# MainBorad.net
KiCad netlist of a schematic drawn in Altium Designer
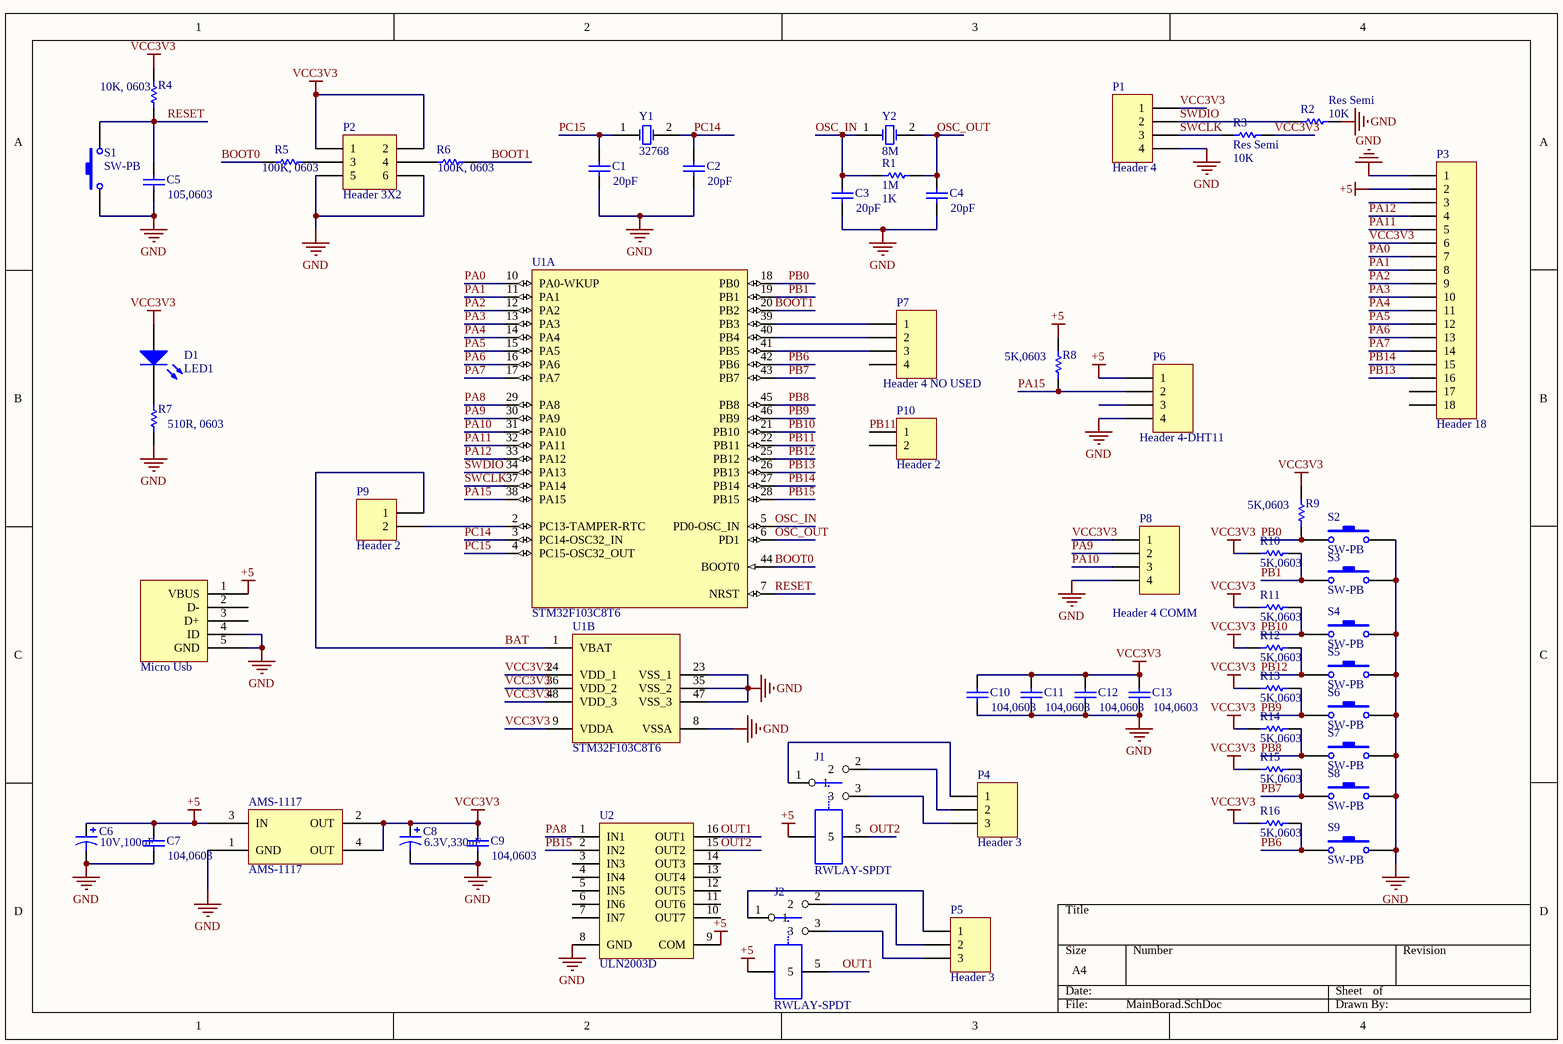
[diagram p0: MainBorad.SchDoc]

(export (version "E")
  (design (tool "Eeschema 10.0.6"))
  (components
    (comp (ref "AMS-1117")
      (value "AMS-1117")
      (footprint "SOT223")
      (libsource (lib "ams1117") (part "AMS-1117"))
    )
    (comp (ref "C1")
      (value "20pF")
      (footprint "0805C")
      (description "Capacitor (Semiconductor SIM Model)")
      (fields (field (name "Comment") "Cap Semi") (field (name "PUBLISHER") "Altium Limited"))
      (libsource (lib "Miscellaneous Devices") (part "Cap Semi"))
    )
    (comp (ref "C2")
      (value "20pF")
      (footprint "0805C")
      (description "Capacitor (Semiconductor SIM Model)")
      (fields (field (name "Comment") "Cap Semi") (field (name "PUBLISHER") "Altium Limited"))
      (libsource (lib "Miscellaneous Devices") (part "Cap Semi"))
    )
    (comp (ref "C3")
      (value "20pF")
      (footprint "0805C")
      (description "Capacitor (Semiconductor SIM Model)")
      (fields (field (name "Comment") "Cap Semi") (field (name "PUBLISHER") "Altium Limited"))
      (libsource (lib "Miscellaneous Devices") (part "Cap Semi"))
    )
    (comp (ref "C4")
      (value "20pF")
      (footprint "0805C")
      (description "Capacitor (Semiconductor SIM Model)")
      (fields (field (name "Comment") "Cap Semi") (field (name "PUBLISHER") "Altium Limited"))
      (libsource (lib "Miscellaneous Devices") (part "Cap Semi"))
    )
    (comp (ref "C5")
      (value "105,0603")
      (footprint "0805C")
      (description "Capacitor (Semiconductor SIM Model)")
      (fields (field (name "Comment") "Cap Semi") (field (name "PUBLISHER") "Altium Limited"))
      (libsource (lib "Miscellaneous Devices") (part "Cap Semi"))
    )
    (comp (ref "C6")
      (value "10V,100uF")
      (footprint "7343C")
      (description "Polarized Capacitor (Surface Mount)")
      (fields (field (name "Comment") "Cap Pol3") (field (name "PUBLISHER") "Altium Limited"))
      (libsource (lib "Miscellaneous Devices") (part "Cap Pol3"))
    )
    (comp (ref "C7")
      (value "104,0603")
      (footprint "0805C")
      (description "Capacitor (Semiconductor SIM Model)")
      (fields (field (name "Comment") "Cap Semi") (field (name "PUBLISHER") "Altium Limited"))
      (libsource (lib "Miscellaneous Devices") (part "Cap Semi"))
    )
    (comp (ref "C8")
      (value "6.3V,330uF")
      (footprint "7343C")
      (description "Polarized Capacitor (Surface Mount)")
      (fields (field (name "PUBLISHER") "Altium Limited"))
      (libsource (lib "Miscellaneous Devices") (part "Cap Pol3"))
    )
    (comp (ref "C9")
      (value "104,0603")
      (footprint "0805C")
      (description "Capacitor (Semiconductor SIM Model)")
      (fields (field (name "Comment") "Cap Semi") (field (name "PUBLISHER") "Altium Limited"))
      (libsource (lib "Miscellaneous Devices") (part "Cap Semi"))
    )
    (comp (ref "C10")
      (value "104,0603")
      (footprint "0805C")
      (description "Capacitor (Semiconductor SIM Model)")
      (fields (field (name "Comment") "Cap Semi") (field (name "PUBLISHER") "Altium Limited"))
      (libsource (lib "Miscellaneous Devices") (part "Cap Semi"))
    )
    (comp (ref "C11")
      (value "104,0603")
      (footprint "0805C")
      (description "Capacitor (Semiconductor SIM Model)")
      (fields (field (name "Comment") "Cap Semi") (field (name "PUBLISHER") "Altium Limited"))
      (libsource (lib "Miscellaneous Devices") (part "Cap Semi"))
    )
    (comp (ref "C12")
      (value "104,0603")
      (footprint "0805C")
      (description "Capacitor (Semiconductor SIM Model)")
      (fields (field (name "Comment") "Cap Semi") (field (name "PUBLISHER") "Altium Limited"))
      (libsource (lib "Miscellaneous Devices") (part "Cap Semi"))
    )
    (comp (ref "C13")
      (value "104,0603")
      (footprint "0805C")
      (description "Capacitor (Semiconductor SIM Model)")
      (fields (field (name "Comment") "Cap Semi") (field (name "PUBLISHER") "Altium Limited"))
      (libsource (lib "Miscellaneous Devices") (part "Cap Semi"))
    )
    (comp (ref "D1")
      (value "LED1")
      (footprint "0805")
      (description "Typical RED GaAs LED")
      (fields (field (name "PUBLISHER") "Altium Limited"))
      (libsource (lib "Miscellaneous Devices") (part "LED1"))
    )
    (comp (ref "J1") (value "RWLAY-SPDT") (footprint "relay") (libsource (lib "J继电器") (part "RWLAY-SPDT")))
    (comp (ref "J2") (value "RWLAY-SPDT") (footprint "relay") (libsource (lib "J继电器") (part "RWLAY-SPDT")))
    (comp (ref "Micro Usb")
      (value "Micro Usb")
      (footprint "Micro_USB")
      (libsource (lib "micro_usb") (part "Micro Usb"))
    )
    (comp (ref "P1")
      (value "Header 4")
      (footprint "HDR1X4")
      (description "Header, 4-Pin")
      (fields (field (name "PUBLISHER") "Altium Limited"))
      (libsource (lib "Miscellaneous Connectors") (part "Header 4"))
    )
    (comp (ref "P2")
      (value "Header 3X2")
      (footprint "HDR2X3")
      (description "Header, 3-Pin, Dual row")
      (fields (field (name "PUBLISHER") "Altium Limited"))
      (libsource (lib "Miscellaneous Connectors") (part "Header 3X2"))
    )
    (comp (ref "P3")
      (value "Header 18")
      (footprint "HDR1X18")
      (description "Header, 18-Pin")
      (fields (field (name "PUBLISHER") "Altium Limited"))
      (libsource (lib "Miscellaneous Connectors") (part "Header 18"))
    )
    (comp (ref "P4")
      (value "Header 3")
      (footprint "HDR1X3")
      (description "Header, 3-Pin")
      (fields (field (name "PUBLISHER") "Altium Limited"))
      (libsource (lib "Miscellaneous Connectors") (part "Header 3"))
    )
    (comp (ref "P5")
      (value "Header 3")
      (footprint "HDR1X3")
      (description "Header, 3-Pin")
      (fields (field (name "PUBLISHER") "Altium Limited"))
      (libsource (lib "Miscellaneous Connectors") (part "Header 3"))
    )
    (comp (ref "P6")
      (value "Header 4-DHT11")
      (footprint "HDR1X4")
      (description "Header, 4-Pin")
      (fields (field (name "PUBLISHER") "Altium Limited"))
      (libsource (lib "") (part "Header 4_1"))
    )
    (comp (ref "P7")
      (value "Header 4 NO USED")
      (footprint "HDR1X4")
      (description "Header, 4-Pin")
      (fields (field (name "PUBLISHER") "Altium Limited"))
      (libsource (lib "") (part "Header 4_1"))
    )
    (comp (ref "P8")
      (value "Header 4 COMM")
      (footprint "HDR1X4")
      (description "Header, 4-Pin")
      (fields (field (name "PUBLISHER") "Altium Limited"))
      (libsource (lib "") (part "Header 4_1"))
    )
    (comp (ref "P9")
      (value "Header 2")
      (footprint "HDR1X2")
      (description "Header, 2-Pin")
      (fields (field (name "PUBLISHER") "Altium Limited"))
      (libsource (lib "") (part "Header 2_1"))
    )
    (comp (ref "P10")
      (value "Header 2")
      (footprint "HDR1X2")
      (description "Header, 2-Pin")
      (fields (field (name "PUBLISHER") "Altium Limited"))
      (libsource (lib "Miscellaneous Connectors") (part "Header 2"))
    )
    (comp (ref "R1")
      (value "1M")
      (footprint "0805R")
      (description "Semiconductor Resistor")
      (fields (field (name "ALTIUM_VALUE") "1K") (field (name "PUBLISHER") "Altium Limited"))
      (libsource (lib "Miscellaneous Devices") (part "Res Semi"))
    )
    (comp (ref "R2")
      (value "Res Semi")
      (footprint "0805R")
      (description "Semiconductor Resistor")
      (fields (field (name "ALTIUM_VALUE") "10K") (field (name "PUBLISHER") "Altium Limited"))
      (libsource (lib "Miscellaneous Devices") (part "Res Semi"))
    )
    (comp (ref "R3")
      (value "Res Semi")
      (footprint "0805R")
      (description "Semiconductor Resistor")
      (fields (field (name "ALTIUM_VALUE") "10K") (field (name "PUBLISHER") "Altium Limited"))
      (libsource (lib "Miscellaneous Devices") (part "Res Semi"))
    )
    (comp (ref "R4")
      (value "10K, 0603")
      (footprint "0805R")
      (description "Semiconductor Resistor")
      (fields (field (name "Comment") "Res Semi") (field (name "PUBLISHER") "Altium Limited"))
      (libsource (lib "Miscellaneous Devices") (part "Res Semi"))
    )
    (comp (ref "R5")
      (value "100K, 0603")
      (footprint "0805R")
      (description "Semiconductor Resistor")
      (fields (field (name "Comment") "Res Semi") (field (name "PUBLISHER") "Altium Limited"))
      (libsource (lib "Miscellaneous Devices") (part "Res Semi"))
    )
    (comp (ref "R6")
      (value "100K, 0603")
      (footprint "0805R")
      (description "Semiconductor Resistor")
      (fields (field (name "Comment") "Res Semi") (field (name "PUBLISHER") "Altium Limited"))
      (libsource (lib "Miscellaneous Devices") (part "Res Semi"))
    )
    (comp (ref "R7")
      (value "510R, 0603")
      (footprint "0805R")
      (description "Semiconductor Resistor")
      (fields (field (name "Comment") "Res Semi") (field (name "PUBLISHER") "Altium Limited"))
      (libsource (lib "Miscellaneous Devices") (part "Res Semi"))
    )
    (comp (ref "R8")
      (value "5K,0603")
      (footprint "0805R")
      (description "Semiconductor Resistor")
      (fields (field (name "Comment") "Res Semi") (field (name "PUBLISHER") "Altium Limited"))
      (libsource (lib "Miscellaneous Devices") (part "Res Semi"))
    )
    (comp (ref "R9")
      (value "5K,0603")
      (footprint "0805R")
      (description "Semiconductor Resistor")
      (fields (field (name "Comment") "Res Semi") (field (name "PUBLISHER") "Altium Limited"))
      (libsource (lib "Miscellaneous Devices") (part "Res Semi"))
    )
    (comp (ref "R10")
      (value "5K,0603")
      (footprint "0805R")
      (description "Semiconductor Resistor")
      (fields (field (name "Comment") "Res Semi") (field (name "PUBLISHER") "Altium Limited"))
      (libsource (lib "Miscellaneous Devices") (part "Res Semi"))
    )
    (comp (ref "R11")
      (value "5K,0603")
      (footprint "0805R")
      (description "Semiconductor Resistor")
      (fields (field (name "Comment") "Res Semi") (field (name "PUBLISHER") "Altium Limited"))
      (libsource (lib "Miscellaneous Devices") (part "Res Semi"))
    )
    (comp (ref "R12")
      (value "5K,0603")
      (footprint "0805R")
      (description "Semiconductor Resistor")
      (fields (field (name "Comment") "Res Semi") (field (name "PUBLISHER") "Altium Limited"))
      (libsource (lib "Miscellaneous Devices") (part "Res Semi"))
    )
    (comp (ref "R13")
      (value "5K,0603")
      (footprint "0805R")
      (description "Semiconductor Resistor")
      (fields (field (name "Comment") "Res Semi") (field (name "PUBLISHER") "Altium Limited"))
      (libsource (lib "Miscellaneous Devices") (part "Res Semi"))
    )
    (comp (ref "R14")
      (value "5K,0603")
      (footprint "0805R")
      (description "Semiconductor Resistor")
      (fields (field (name "Comment") "Res Semi") (field (name "PUBLISHER") "Altium Limited"))
      (libsource (lib "Miscellaneous Devices") (part "Res Semi"))
    )
    (comp (ref "R15")
      (value "5K,0603")
      (footprint "0805R")
      (description "Semiconductor Resistor")
      (fields (field (name "Comment") "Res Semi") (field (name "PUBLISHER") "Altium Limited"))
      (libsource (lib "Miscellaneous Devices") (part "Res Semi"))
    )
    (comp (ref "R16")
      (value "5K,0603")
      (footprint "0805R")
      (description "Semiconductor Resistor")
      (fields (field (name "Comment") "Res Semi") (field (name "PUBLISHER") "Altium Limited"))
      (libsource (lib "Miscellaneous Devices") (part "Res Semi"))
    )
    (comp (ref "S1")
      (value "SW-PB")
      (footprint "SPST-2")
      (description "Switch")
      (fields (field (name "PUBLISHER") "Altium Limited"))
      (libsource (lib "Miscellaneous Devices") (part "SW-PB"))
    )
    (comp (ref "S2")
      (value "SW-PB")
      (footprint "SPST-2")
      (description "Switch")
      (fields (field (name "PUBLISHER") "Altium Limited"))
      (libsource (lib "Miscellaneous Devices") (part "SW-PB"))
    )
    (comp (ref "S3")
      (value "SW-PB")
      (footprint "SPST-2")
      (description "Switch")
      (fields (field (name "PUBLISHER") "Altium Limited"))
      (libsource (lib "Miscellaneous Devices") (part "SW-PB"))
    )
    (comp (ref "S4")
      (value "SW-PB")
      (footprint "SPST-2")
      (description "Switch")
      (fields (field (name "PUBLISHER") "Altium Limited"))
      (libsource (lib "Miscellaneous Devices") (part "SW-PB"))
    )
    (comp (ref "S5")
      (value "SW-PB")
      (footprint "SPST-2")
      (description "Switch")
      (fields (field (name "PUBLISHER") "Altium Limited"))
      (libsource (lib "Miscellaneous Devices") (part "SW-PB"))
    )
    (comp (ref "S6")
      (value "SW-PB")
      (footprint "SPST-2")
      (description "Switch")
      (fields (field (name "PUBLISHER") "Altium Limited"))
      (libsource (lib "Miscellaneous Devices") (part "SW-PB"))
    )
    (comp (ref "S7")
      (value "SW-PB")
      (footprint "SPST-2")
      (description "Switch")
      (fields (field (name "PUBLISHER") "Altium Limited"))
      (libsource (lib "Miscellaneous Devices") (part "SW-PB"))
    )
    (comp (ref "S8")
      (value "SW-PB")
      (footprint "SPST-2")
      (description "Switch")
      (fields (field (name "PUBLISHER") "Altium Limited"))
      (libsource (lib "Miscellaneous Devices") (part "SW-PB"))
    )
    (comp (ref "S9")
      (value "SW-PB")
      (footprint "SPST-2")
      (description "Switch")
      (fields (field (name "PUBLISHER") "Altium Limited"))
      (libsource (lib "Miscellaneous Devices") (part "SW-PB"))
    )
    (comp (ref "U1")
      (value "STM32F103C8T6")
      (footprint "LQFP48_N")
      (libsource (lib "STMicroelectronics STM32 F1") (part "STM32F103C8T6"))
    )
    (comp (ref "U2")
      (value "ULN2003D")
      (footprint "SO16_N")
      (description "Seven Darlington Array")
      (fields (field (name "PUBLISHER") "Altium Limited"))
      (libsource (lib "ST Interface Darlington Driver") (part "ULN2003D"))
    )
    (comp (ref "Y1")
      (value "32768")
      (footprint "R38")
      (description "Crystal Oscillator")
      (fields (field (name "PUBLISHER") "Altium Limited"))
      (libsource (lib "Miscellaneous Devices") (part "XTAL"))
    )
    (comp (ref "Y2")
      (value "8M")
      (footprint "XTAL1")
      (description "Crystal Oscillator")
      (fields (field (name "PUBLISHER") "Altium Limited"))
      (libsource (lib "Miscellaneous Devices") (part "XTAL"))
    )
  )
  (nets
    (net (code "1") (name "+5") (class "Default")
      (node (ref "AMS-1117") (pin "3") (pinfunction "IN_3") (pintype "passive"))
      (node (ref "C6") (pin "1") (pinfunction "1_1") (pintype "passive"))
      (node (ref "C7") (pin "2") (pinfunction "2_2") (pintype "passive"))
      (node (ref "J1") (pin "4") (pinfunction "4_4") (pintype "passive"))
      (node (ref "J2") (pin "4") (pinfunction "4_4") (pintype "passive"))
      (node (ref "Micro Usb") (pin "1") (pinfunction "VBUS_1") (pintype "passive"))
      (node (ref "P3") (pin "2") (pinfunction "2_2") (pintype "passive"))
      (node (ref "P6") (pin "1") (pinfunction "1_1") (pintype "passive"))
      (node (ref "R8") (pin "2") (pinfunction "2_2") (pintype "passive"))
      (node (ref "U2") (pin "9") (pinfunction "COM_9") (pintype "passive"))
    )
    (net (code "2") (name "/BAT") (class "Default")
      (node (ref "P9") (pin "1") (pinfunction "1_1") (pintype "passive"))
      (node (ref "U1") (pin "1") (pinfunction "VBAT_1") (pintype "power_in"))
    )
    (net (code "3") (name "/BOOT0") (class "Default")
      (node (ref "R5") (pin "2") (pinfunction "2_2") (pintype "passive"))
      (node (ref "U1") (pin "44") (pinfunction "BOOT0_44") (pintype "input"))
    )
    (net (code "4") (name "/BOOT1") (class "Default")
      (node (ref "R6") (pin "1") (pinfunction "1_1") (pintype "passive"))
      (node (ref "U1") (pin "20") (pinfunction "PB2_20") (pintype "bidirectional"))
    )
    (net (code "5") (name "/OSC_IN") (class "Default")
      (node (ref "C3") (pin "2") (pinfunction "2_2") (pintype "passive"))
      (node (ref "R1") (pin "1") (pinfunction "1_1") (pintype "passive"))
      (node (ref "U1") (pin "5") (pinfunction "PD0-OSC_IN_5") (pintype "bidirectional"))
      (node (ref "Y2") (pin "1") (pinfunction "OSC1_1") (pintype "passive"))
    )
    (net (code "6") (name "/OSC_OUT") (class "Default")
      (node (ref "C4") (pin "2") (pinfunction "2_2") (pintype "passive"))
      (node (ref "R1") (pin "2") (pinfunction "2_2") (pintype "passive"))
      (node (ref "U1") (pin "6") (pinfunction "PD1_6") (pintype "bidirectional"))
      (node (ref "Y2") (pin "2") (pinfunction "OSC2_2") (pintype "passive"))
    )
    (net (code "7") (name "/OUT1") (class "Default")
      (node (ref "J2") (pin "5") (pinfunction "5_5") (pintype "passive"))
      (node (ref "U2") (pin "16") (pinfunction "OUT1_16") (pintype "open_collector"))
    )
    (net (code "8") (name "/OUT2") (class "Default")
      (node (ref "J1") (pin "5") (pinfunction "5_5") (pintype "passive"))
      (node (ref "U2") (pin "15") (pinfunction "OUT2_15") (pintype "open_collector"))
    )
    (net (code "9") (name "/PA0") (class "Default")
      (node (ref "P3") (pin "7") (pinfunction "7_7") (pintype "passive"))
      (node (ref "U1") (pin "10") (pinfunction "PA0-WKUP_10") (pintype "bidirectional"))
    )
    (net (code "10") (name "/PA1") (class "Default")
      (node (ref "P3") (pin "8") (pinfunction "8_8") (pintype "passive"))
      (node (ref "U1") (pin "11") (pinfunction "PA1_11") (pintype "bidirectional"))
    )
    (net (code "11") (name "/PA2") (class "Default")
      (node (ref "P3") (pin "9") (pinfunction "9_9") (pintype "passive"))
      (node (ref "U1") (pin "12") (pinfunction "PA2_12") (pintype "bidirectional"))
    )
    (net (code "12") (name "/PA3") (class "Default")
      (node (ref "P3") (pin "10") (pinfunction "10_10") (pintype "passive"))
      (node (ref "U1") (pin "13") (pinfunction "PA3_13") (pintype "bidirectional"))
    )
    (net (code "13") (name "/PA4") (class "Default")
      (node (ref "P3") (pin "11") (pinfunction "11_11") (pintype "passive"))
      (node (ref "U1") (pin "14") (pinfunction "PA4_14") (pintype "bidirectional"))
    )
    (net (code "14") (name "/PA5") (class "Default")
      (node (ref "P3") (pin "12") (pinfunction "12_12") (pintype "passive"))
      (node (ref "U1") (pin "15") (pinfunction "PA5_15") (pintype "bidirectional"))
    )
    (net (code "15") (name "/PA6") (class "Default")
      (node (ref "P3") (pin "13") (pinfunction "13_13") (pintype "passive"))
      (node (ref "U1") (pin "16") (pinfunction "PA6_16") (pintype "bidirectional"))
    )
    (net (code "16") (name "/PA7") (class "Default")
      (node (ref "P3") (pin "14") (pinfunction "14_14") (pintype "passive"))
      (node (ref "U1") (pin "17") (pinfunction "PA7_17") (pintype "bidirectional"))
    )
    (net (code "17") (name "/PA8") (class "Default")
      (node (ref "U1") (pin "29") (pinfunction "PA8_29") (pintype "bidirectional"))
      (node (ref "U2") (pin "1") (pinfunction "IN1_1") (pintype "passive"))
    )
    (net (code "18") (name "/PA9") (class "Default")
      (node (ref "P8") (pin "2") (pinfunction "2_2") (pintype "passive"))
      (node (ref "U1") (pin "30") (pinfunction "PA9_30") (pintype "bidirectional"))
    )
    (net (code "19") (name "/PA10") (class "Default")
      (node (ref "P8") (pin "3") (pinfunction "3_3") (pintype "passive"))
      (node (ref "U1") (pin "31") (pinfunction "PA10_31") (pintype "bidirectional"))
    )
    (net (code "20") (name "/PA11") (class "Default")
      (node (ref "P3") (pin "5") (pinfunction "5_5") (pintype "passive"))
      (node (ref "U1") (pin "32") (pinfunction "PA11_32") (pintype "bidirectional"))
    )
    (net (code "21") (name "/PA12") (class "Default")
      (node (ref "P3") (pin "4") (pinfunction "4_4") (pintype "passive"))
      (node (ref "U1") (pin "33") (pinfunction "PA12_33") (pintype "bidirectional"))
    )
    (net (code "22") (name "/PA15") (class "Default")
      (node (ref "P6") (pin "2") (pinfunction "2_2") (pintype "passive"))
      (node (ref "R8") (pin "1") (pinfunction "1_1") (pintype "passive"))
      (node (ref "U1") (pin "38") (pinfunction "PA15_38") (pintype "bidirectional"))
    )
    (net (code "23") (name "/PB0") (class "Default")
      (node (ref "R9") (pin "1") (pinfunction "1_1") (pintype "passive"))
      (node (ref "S2") (pin "1") (pinfunction "1_1") (pintype "passive"))
      (node (ref "U1") (pin "18") (pinfunction "PB0_18") (pintype "bidirectional"))
    )
    (net (code "24") (name "/PB1") (class "Default")
      (node (ref "R10") (pin "1") (pinfunction "1_1") (pintype "passive"))
      (node (ref "S3") (pin "1") (pinfunction "1_1") (pintype "passive"))
      (node (ref "U1") (pin "19") (pinfunction "PB1_19") (pintype "bidirectional"))
    )
    (net (code "25") (name "/PB6") (class "Default")
      (node (ref "R16") (pin "1") (pinfunction "1_1") (pintype "passive"))
      (node (ref "S9") (pin "1") (pinfunction "1_1") (pintype "passive"))
      (node (ref "U1") (pin "42") (pinfunction "PB6_42") (pintype "bidirectional"))
    )
    (net (code "26") (name "/PB7") (class "Default")
      (node (ref "R15") (pin "1") (pinfunction "1_1") (pintype "passive"))
      (node (ref "S8") (pin "1") (pinfunction "1_1") (pintype "passive"))
      (node (ref "U1") (pin "43") (pinfunction "PB7_43") (pintype "bidirectional"))
    )
    (net (code "27") (name "/PB8") (class "Default")
      (node (ref "R14") (pin "1") (pinfunction "1_1") (pintype "passive"))
      (node (ref "S7") (pin "1") (pinfunction "1_1") (pintype "passive"))
      (node (ref "U1") (pin "45") (pinfunction "PB8_45") (pintype "bidirectional"))
    )
    (net (code "28") (name "/PB9") (class "Default")
      (node (ref "R13") (pin "1") (pinfunction "1_1") (pintype "passive"))
      (node (ref "S6") (pin "1") (pinfunction "1_1") (pintype "passive"))
      (node (ref "U1") (pin "46") (pinfunction "PB9_46") (pintype "bidirectional"))
    )
    (net (code "29") (name "/PB10") (class "Default")
      (node (ref "R11") (pin "1") (pinfunction "1_1") (pintype "passive"))
      (node (ref "S4") (pin "1") (pinfunction "1_1") (pintype "passive"))
      (node (ref "U1") (pin "21") (pinfunction "PB10_21") (pintype "bidirectional"))
    )
    (net (code "30") (name "/PB11") (class "Default")
      (node (ref "P10") (pin "1") (pinfunction "1_1") (pintype "passive"))
      (node (ref "U1") (pin "22") (pinfunction "PB11_22") (pintype "bidirectional"))
    )
    (net (code "31") (name "/PB12") (class "Default")
      (node (ref "R12") (pin "1") (pinfunction "1_1") (pintype "passive"))
      (node (ref "S5") (pin "1") (pinfunction "1_1") (pintype "passive"))
      (node (ref "U1") (pin "25") (pinfunction "PB12_25") (pintype "bidirectional"))
    )
    (net (code "32") (name "/PB13") (class "Default")
      (node (ref "P3") (pin "16") (pinfunction "16_16") (pintype "passive"))
      (node (ref "U1") (pin "26") (pinfunction "PB13_26") (pintype "bidirectional"))
    )
    (net (code "33") (name "/PB14") (class "Default")
      (node (ref "P3") (pin "15") (pinfunction "15_15") (pintype "passive"))
      (node (ref "U1") (pin "27") (pinfunction "PB14_27") (pintype "bidirectional"))
    )
    (net (code "34") (name "/PB15") (class "Default")
      (node (ref "U1") (pin "28") (pinfunction "PB15_28") (pintype "bidirectional"))
      (node (ref "U2") (pin "2") (pinfunction "IN2_2") (pintype "passive"))
    )
    (net (code "35") (name "/PC14") (class "Default")
      (node (ref "C2") (pin "2") (pinfunction "2_2") (pintype "passive"))
      (node (ref "U1") (pin "3") (pinfunction "PC14-OSC32_IN_3") (pintype "bidirectional"))
      (node (ref "Y1") (pin "2") (pinfunction "OSC2_2") (pintype "passive"))
    )
    (net (code "36") (name "/PC15") (class "Default")
      (node (ref "C1") (pin "2") (pinfunction "2_2") (pintype "passive"))
      (node (ref "U1") (pin "4") (pinfunction "PC15-OSC32_OUT_4") (pintype "bidirectional"))
      (node (ref "Y1") (pin "1") (pinfunction "OSC1_1") (pintype "passive"))
    )
    (net (code "37") (name "/RESET") (class "Default")
      (node (ref "C5") (pin "2") (pinfunction "2_2") (pintype "passive"))
      (node (ref "R4") (pin "1") (pinfunction "1_1") (pintype "passive"))
      (node (ref "S1") (pin "2") (pinfunction "2_2") (pintype "passive"))
      (node (ref "U1") (pin "7") (pinfunction "NRST_7") (pintype "bidirectional"))
    )
    (net (code "38") (name "/SWCLK") (class "Default")
      (node (ref "P1") (pin "3") (pinfunction "3_3") (pintype "passive"))
      (node (ref "R3") (pin "2") (pinfunction "2_2") (pintype "passive"))
      (node (ref "U1") (pin "37") (pinfunction "PA14_37") (pintype "bidirectional"))
    )
    (net (code "39") (name "/SWDIO") (class "Default")
      (node (ref "P1") (pin "2") (pinfunction "2_2") (pintype "passive"))
      (node (ref "R2") (pin "2") (pinfunction "2_2") (pintype "passive"))
      (node (ref "U1") (pin "34") (pinfunction "PA13_34") (pintype "bidirectional"))
    )
    (net (code "40") (name "GND") (class "Default")
      (node (ref "AMS-1117") (pin "1") (pinfunction "GND_1") (pintype "power_in"))
      (node (ref "C1") (pin "1") (pinfunction "1_1") (pintype "passive"))
      (node (ref "C10") (pin "1") (pinfunction "1_1") (pintype "passive"))
      (node (ref "C11") (pin "1") (pinfunction "1_1") (pintype "passive"))
      (node (ref "C12") (pin "1") (pinfunction "1_1") (pintype "passive"))
      (node (ref "C13") (pin "1") (pinfunction "1_1") (pintype "passive"))
      (node (ref "C2") (pin "1") (pinfunction "1_1") (pintype "passive"))
      (node (ref "C3") (pin "1") (pinfunction "1_1") (pintype "passive"))
      (node (ref "C4") (pin "1") (pinfunction "1_1") (pintype "passive"))
      (node (ref "C5") (pin "1") (pinfunction "1_1") (pintype "passive"))
      (node (ref "C6") (pin "2") (pinfunction "2_2") (pintype "passive"))
      (node (ref "C7") (pin "1") (pinfunction "1_1") (pintype "passive"))
      (node (ref "C8") (pin "2") (pinfunction "2_2") (pintype "passive"))
      (node (ref "C9") (pin "1") (pinfunction "1_1") (pintype "passive"))
      (node (ref "Micro Usb") (pin "4") (pinfunction "ID_4") (pintype "passive"))
      (node (ref "Micro Usb") (pin "5") (pinfunction "GND_5") (pintype "passive"))
      (node (ref "P1") (pin "4") (pinfunction "4_4") (pintype "passive"))
      (node (ref "P2") (pin "5") (pinfunction "5_5") (pintype "passive"))
      (node (ref "P2") (pin "6") (pinfunction "6_6") (pintype "passive"))
      (node (ref "P3") (pin "1") (pinfunction "1_1") (pintype "passive"))
      (node (ref "P6") (pin "4") (pinfunction "4_4") (pintype "passive"))
      (node (ref "P8") (pin "4") (pinfunction "4_4") (pintype "passive"))
      (node (ref "R2") (pin "1") (pinfunction "1_1") (pintype "passive"))
      (node (ref "R7") (pin "1") (pinfunction "1_1") (pintype "passive"))
      (node (ref "S1") (pin "1") (pinfunction "1_1") (pintype "passive"))
      (node (ref "S2") (pin "2") (pinfunction "2_2") (pintype "passive"))
      (node (ref "S3") (pin "2") (pinfunction "2_2") (pintype "passive"))
      (node (ref "S4") (pin "2") (pinfunction "2_2") (pintype "passive"))
      (node (ref "S5") (pin "2") (pinfunction "2_2") (pintype "passive"))
      (node (ref "S6") (pin "2") (pinfunction "2_2") (pintype "passive"))
      (node (ref "S7") (pin "2") (pinfunction "2_2") (pintype "passive"))
      (node (ref "S8") (pin "2") (pinfunction "2_2") (pintype "passive"))
      (node (ref "S9") (pin "2") (pinfunction "2_2") (pintype "passive"))
      (node (ref "U1") (pin "23") (pinfunction "VSS_1_23") (pintype "power_in"))
      (node (ref "U1") (pin "35") (pinfunction "VSS_2_35") (pintype "power_in"))
      (node (ref "U1") (pin "47") (pinfunction "VSS_3_47") (pintype "power_in"))
      (node (ref "U1") (pin "8") (pinfunction "VSSA_8") (pintype "power_in"))
      (node (ref "U2") (pin "8") (pinfunction "GND_8") (pintype "power_in"))
    )
    (net (code "41") (name "Net-(D1-K)") (class "Default")
      (node (ref "D1") (pin "2") (pinfunction "K_2") (pintype "passive"))
      (node (ref "R7") (pin "2") (pinfunction "2_2") (pintype "passive"))
    )
    (net (code "42") (name "Net-(J1-Pad1)") (class "Default")
      (node (ref "J1") (pin "1") (pinfunction "1_1") (pintype "passive"))
      (node (ref "P4") (pin "1") (pinfunction "1_1") (pintype "passive"))
    )
    (net (code "43") (name "Net-(J1-Pad2)") (class "Default")
      (node (ref "J1") (pin "2") (pinfunction "2_2") (pintype "passive"))
      (node (ref "P4") (pin "2") (pinfunction "2_2") (pintype "passive"))
    )
    (net (code "44") (name "Net-(J1-Pad3)") (class "Default")
      (node (ref "J1") (pin "3") (pinfunction "3_3") (pintype "passive"))
      (node (ref "P4") (pin "3") (pinfunction "3_3") (pintype "passive"))
    )
    (net (code "45") (name "Net-(J2-Pad1)") (class "Default")
      (node (ref "J2") (pin "1") (pinfunction "1_1") (pintype "passive"))
      (node (ref "P5") (pin "1") (pinfunction "1_1") (pintype "passive"))
    )
    (net (code "46") (name "Net-(J2-Pad2)") (class "Default")
      (node (ref "J2") (pin "2") (pinfunction "2_2") (pintype "passive"))
      (node (ref "P5") (pin "2") (pinfunction "2_2") (pintype "passive"))
    )
    (net (code "47") (name "Net-(J2-Pad3)") (class "Default")
      (node (ref "J2") (pin "3") (pinfunction "3_3") (pintype "passive"))
      (node (ref "P5") (pin "3") (pinfunction "3_3") (pintype "passive"))
    )
    (net (code "48") (name "Net-(P2-Pad3)") (class "Default")
      (node (ref "P2") (pin "3") (pinfunction "3_3") (pintype "passive"))
      (node (ref "R5") (pin "1") (pinfunction "1_1") (pintype "passive"))
    )
    (net (code "49") (name "Net-(P2-Pad4)") (class "Default")
      (node (ref "P2") (pin "4") (pinfunction "4_4") (pintype "passive"))
      (node (ref "R6") (pin "2") (pinfunction "2_2") (pintype "passive"))
    )
    (net (code "50") (name "Net-(U1A-PB3)") (class "Default")
      (node (ref "P7") (pin "1") (pinfunction "1_1") (pintype "passive"))
      (node (ref "U1") (pin "39") (pinfunction "PB3_39") (pintype "bidirectional"))
    )
    (net (code "51") (name "Net-(U1A-PB4)") (class "Default")
      (node (ref "P7") (pin "2") (pinfunction "2_2") (pintype "passive"))
      (node (ref "U1") (pin "40") (pinfunction "PB4_40") (pintype "bidirectional"))
    )
    (net (code "52") (name "Net-(U1A-PB5)") (class "Default")
      (node (ref "P7") (pin "3") (pinfunction "3_3") (pintype "passive"))
      (node (ref "U1") (pin "41") (pinfunction "PB5_41") (pintype "bidirectional"))
    )
    (net (code "53") (name "Net-(U1A-PC13-TAMPER-RTC)") (class "Default")
      (node (ref "P9") (pin "2") (pinfunction "2_2") (pintype "passive"))
      (node (ref "U1") (pin "2") (pinfunction "PC13-TAMPER-RTC_2") (pintype "bidirectional"))
    )
    (net (code "54") (name "VCC3V3") (class "Default")
      (node (ref "AMS-1117") (pin "2") (pinfunction "OUT_2") (pintype "passive"))
      (node (ref "AMS-1117") (pin "4") (pinfunction "OUT_4") (pintype "passive"))
      (node (ref "C10") (pin "2") (pinfunction "2_2") (pintype "passive"))
      (node (ref "C11") (pin "2") (pinfunction "2_2") (pintype "passive"))
      (node (ref "C12") (pin "2") (pinfunction "2_2") (pintype "passive"))
      (node (ref "C13") (pin "2") (pinfunction "2_2") (pintype "passive"))
      (node (ref "C8") (pin "1") (pinfunction "1_1") (pintype "passive"))
      (node (ref "C9") (pin "2") (pinfunction "2_2") (pintype "passive"))
      (node (ref "D1") (pin "1") (pinfunction "A_1") (pintype "passive"))
      (node (ref "P1") (pin "1") (pinfunction "1_1") (pintype "passive"))
      (node (ref "P2") (pin "1") (pinfunction "1_1") (pintype "passive"))
      (node (ref "P2") (pin "2") (pinfunction "2_2") (pintype "passive"))
      (node (ref "P3") (pin "6") (pinfunction "6_6") (pintype "passive"))
      (node (ref "P8") (pin "1") (pinfunction "1_1") (pintype "passive"))
      (node (ref "R10") (pin "2") (pinfunction "2_2") (pintype "passive"))
      (node (ref "R11") (pin "2") (pinfunction "2_2") (pintype "passive"))
      (node (ref "R12") (pin "2") (pinfunction "2_2") (pintype "passive"))
      (node (ref "R13") (pin "2") (pinfunction "2_2") (pintype "passive"))
      (node (ref "R14") (pin "2") (pinfunction "2_2") (pintype "passive"))
      (node (ref "R15") (pin "2") (pinfunction "2_2") (pintype "passive"))
      (node (ref "R16") (pin "2") (pinfunction "2_2") (pintype "passive"))
      (node (ref "R3") (pin "1") (pinfunction "1_1") (pintype "passive"))
      (node (ref "R4") (pin "2") (pinfunction "2_2") (pintype "passive"))
      (node (ref "R9") (pin "2") (pinfunction "2_2") (pintype "passive"))
      (node (ref "U1") (pin "24") (pinfunction "VDD_1_24") (pintype "power_in"))
      (node (ref "U1") (pin "36") (pinfunction "VDD_2_36") (pintype "power_in"))
      (node (ref "U1") (pin "48") (pinfunction "VDD_3_48") (pintype "power_in"))
      (node (ref "U1") (pin "9") (pinfunction "VDDA_9") (pintype "power_in"))
    )
    (net (code "55") (name "unconnected-(Micro Usb-D+-Pad3)") (class "Default")
      (node (ref "Micro Usb") (pin "3") (pinfunction "D+_3") (pintype "passive"))
    )
    (net (code "56") (name "unconnected-(Micro Usb-D--Pad2)") (class "Default")
      (node (ref "Micro Usb") (pin "2") (pinfunction "D-_2") (pintype "passive"))
    )
    (net (code "57") (name "unconnected-(P3-Pad3)") (class "Default")
      (node (ref "P3") (pin "3") (pinfunction "3_3") (pintype "passive"))
    )
    (net (code "58") (name "unconnected-(P3-Pad17)") (class "Default")
      (node (ref "P3") (pin "17") (pinfunction "17_17") (pintype "passive"))
    )
    (net (code "59") (name "unconnected-(P3-Pad18)") (class "Default")
      (node (ref "P3") (pin "18") (pinfunction "18_18") (pintype "passive"))
    )
    (net (code "60") (name "unconnected-(P6-Pad3)") (class "Default")
      (node (ref "P6") (pin "3") (pinfunction "3_3") (pintype "passive"))
    )
    (net (code "61") (name "unconnected-(P7-Pad4)") (class "Default")
      (node (ref "P7") (pin "4") (pinfunction "4_4") (pintype "passive"))
    )
    (net (code "62") (name "unconnected-(P10-Pad2)") (class "Default")
      (node (ref "P10") (pin "2") (pinfunction "2_2") (pintype "passive"))
    )
    (net (code "63") (name "unconnected-(U2-IN3-Pad3)") (class "Default")
      (node (ref "U2") (pin "3") (pinfunction "IN3_3") (pintype "passive"))
    )
    (net (code "64") (name "unconnected-(U2-IN4-Pad4)") (class "Default")
      (node (ref "U2") (pin "4") (pinfunction "IN4_4") (pintype "passive"))
    )
    (net (code "65") (name "unconnected-(U2-IN5-Pad5)") (class "Default")
      (node (ref "U2") (pin "5") (pinfunction "IN5_5") (pintype "passive"))
    )
    (net (code "66") (name "unconnected-(U2-IN6-Pad6)") (class "Default")
      (node (ref "U2") (pin "6") (pinfunction "IN6_6") (pintype "passive"))
    )
    (net (code "67") (name "unconnected-(U2-IN7-Pad7)") (class "Default")
      (node (ref "U2") (pin "7") (pinfunction "IN7_7") (pintype "passive"))
    )
    (net (code "68") (name "unconnected-(U2-OUT3-Pad14)") (class "Default")
      (node (ref "U2") (pin "14") (pinfunction "OUT3_14") (pintype "open_collector"))
    )
    (net (code "69") (name "unconnected-(U2-OUT4-Pad13)") (class "Default")
      (node (ref "U2") (pin "13") (pinfunction "OUT4_13") (pintype "open_collector"))
    )
    (net (code "70") (name "unconnected-(U2-OUT5-Pad12)") (class "Default")
      (node (ref "U2") (pin "12") (pinfunction "OUT5_12") (pintype "open_collector"))
    )
    (net (code "71") (name "unconnected-(U2-OUT6-Pad11)") (class "Default")
      (node (ref "U2") (pin "11") (pinfunction "OUT6_11") (pintype "open_collector"))
    )
    (net (code "72") (name "unconnected-(U2-OUT7-Pad10)") (class "Default")
      (node (ref "U2") (pin "10") (pinfunction "OUT7_10") (pintype "open_collector"))
    )
  )
)
